# page1.net
KiCad netlist of a schematic drawn in EAGLE
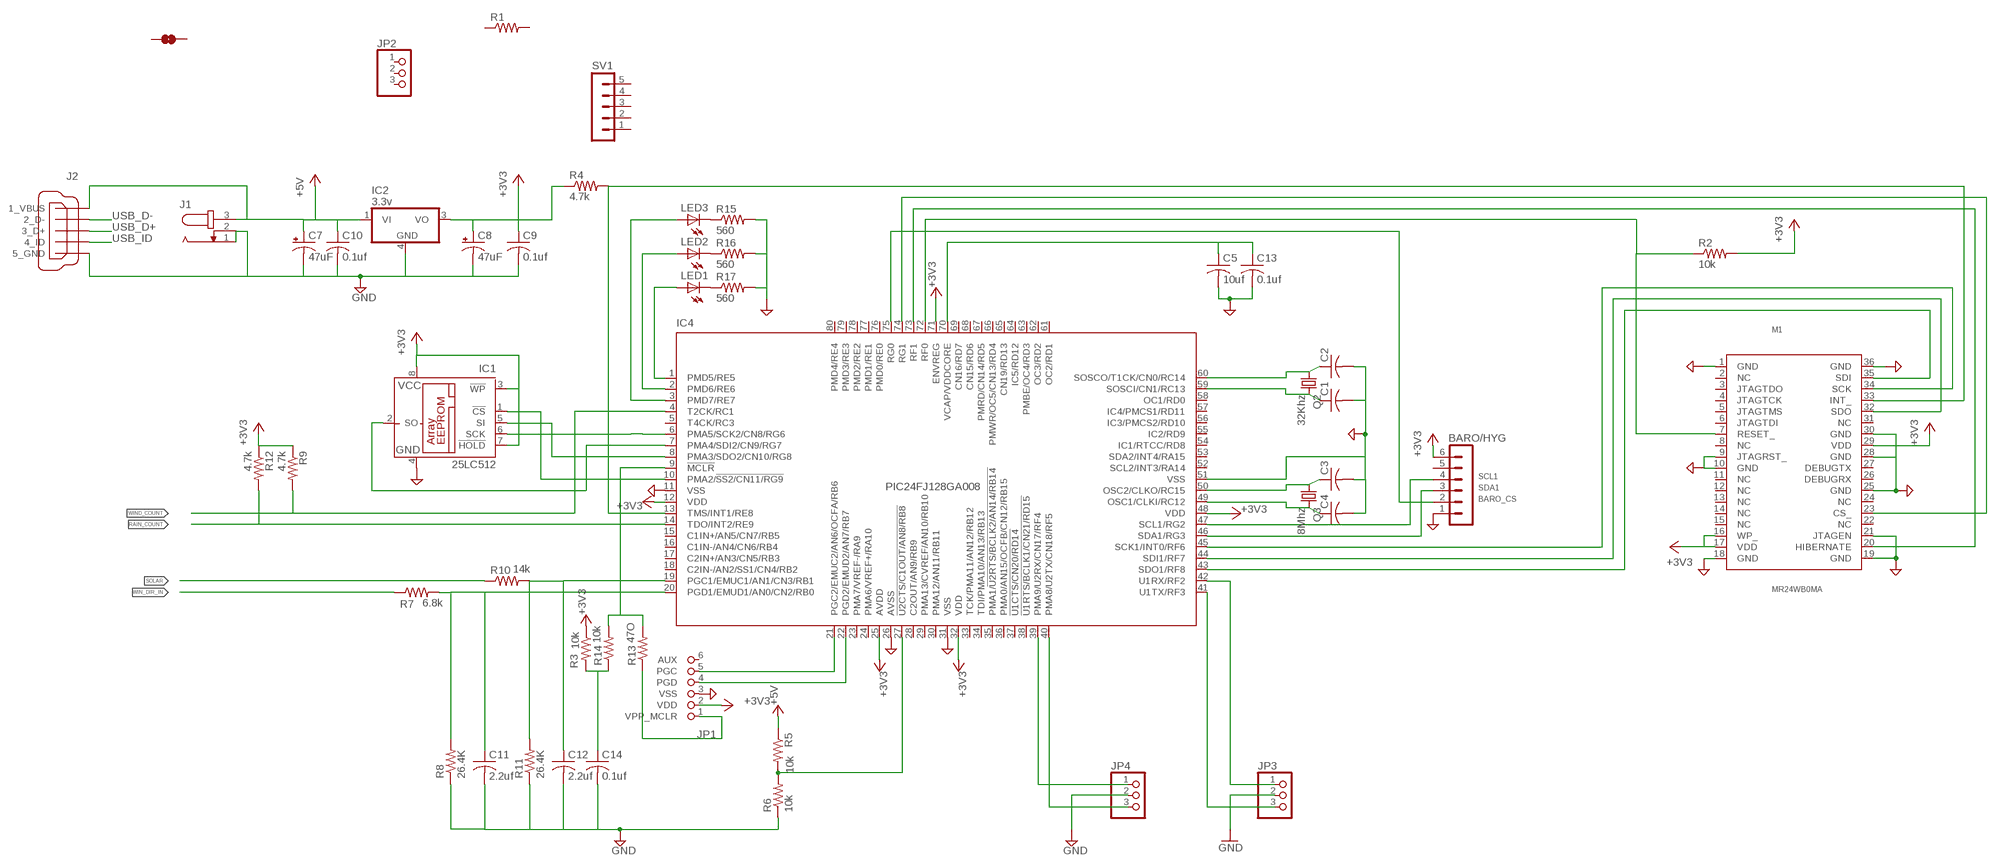
[diagram p0: schematic, sheet 1]

(export (version "E")
  (design (tool "Eeschema 10.0.6"))
  (components
    (comp (ref "BARO/HYG")
      (value "MA06-1")
      (footprint "eagle-import:MA06-1")
      (libsource (lib "eagle-import") (part "MA06-1"))
    )
    (comp (ref "C1")
      (value "C-USC0603")
      (footprint "eagle-import:C0603")
      (libsource (lib "eagle-import") (part "C-USC0603"))
    )
    (comp (ref "C2")
      (value "C-USC0603")
      (footprint "eagle-import:C0603")
      (libsource (lib "eagle-import") (part "C-USC0603"))
    )
    (comp (ref "C3")
      (value "C-USC0603")
      (footprint "eagle-import:C0603")
      (libsource (lib "eagle-import") (part "C-USC0603"))
    )
    (comp (ref "C4")
      (value "C-USC0603")
      (footprint "eagle-import:C0603")
      (libsource (lib "eagle-import") (part "C-USC0603"))
    )
    (comp (ref "C5")
      (value "10uf")
      (footprint "eagle-import:C0805")
      (libsource (lib "eagle-import") (part "C-USC0805"))
    )
    (comp (ref "C7")
      (value "47uF")
      (footprint "eagle-import:140CLH-0810")
      (libsource (lib "eagle-import") (part "CPOL-US140CLH-0810"))
    )
    (comp (ref "C8")
      (value "47uF")
      (footprint "eagle-import:140CLH-0810")
      (libsource (lib "eagle-import") (part "CPOL-US140CLH-0810"))
    )
    (comp (ref "C9")
      (value "0.1uf")
      (footprint "eagle-import:C0805")
      (libsource (lib "eagle-import") (part "C-USC0805"))
    )
    (comp (ref "C10")
      (value "0.1uf")
      (footprint "eagle-import:C0805")
      (libsource (lib "eagle-import") (part "C-USC0805"))
    )
    (comp (ref "C11")
      (value "2.2uf")
      (footprint "eagle-import:C1206")
      (libsource (lib "eagle-import") (part "C-USC1206"))
    )
    (comp (ref "C12")
      (value "2.2uf")
      (footprint "eagle-import:C1206")
      (libsource (lib "eagle-import") (part "C-USC1206"))
    )
    (comp (ref "C13")
      (value "0.1uf")
      (footprint "eagle-import:C0805")
      (libsource (lib "eagle-import") (part "C-USC0805"))
    )
    (comp (ref "C14")
      (value "0.1uf")
      (footprint "eagle-import:C0805")
      (libsource (lib "eagle-import") (part "C-USC0805"))
    )
    (comp (ref "IC1")
      (value "25LC512")
      (footprint "eagle-import:SO-08")
      (fields (field (name "MF") "MICROCHIP") (field (name "MPN") "25LC080/SN"))
      (libsource (lib "eagle-import") (part "25SNLC080"))
    )
    (comp (ref "IC2")
      (value "3.3v")
      (footprint "eagle-import:DPACK")
      (libsource (lib "eagle-import") (part "78MXXL"))
    )
    (comp (ref "IC4")
      (value "PIC24FJ128GA008")
      (footprint "eagle-import:TQFP80-12X12")
      (fields (field (name "MF") "MICROCHIP") (field (name "MPN") "PIC24FJ128GA008-I/PT"))
      (libsource (lib "eagle-import") (part "PIC24FJGA008128"))
    )
    (comp (ref "J1")
      (value "JACK-PLUG0")
      (footprint "eagle-import:SPC4077")
      (libsource (lib "eagle-import") (part "JACK-PLUG0"))
    )
    (comp (ref "J2")
      (value "MINI-USB-32005-201")
      (footprint "eagle-import:32005-201")
      (libsource (lib "eagle-import") (part "MINI-USB-32005-201"))
    )
    (comp (ref "JP1")
      (value "PIKIT2_PRG")
      (footprint "eagle-import:1X06")
      (libsource (lib "eagle-import") (part "PIKIT2_PRG"))
    )
    (comp (ref "JP2")
      (value "PINHD-1X3")
      (footprint "eagle-import:1X03")
      (libsource (lib "eagle-import") (part "PINHD-1X3"))
    )
    (comp (ref "JP3")
      (value "PINHD-1X3")
      (footprint "eagle-import:1X03")
      (libsource (lib "eagle-import") (part "PINHD-1X3"))
    )
    (comp (ref "JP4")
      (value "PINHD-1X3")
      (footprint "eagle-import:1X03")
      (libsource (lib "eagle-import") (part "PINHD-1X3"))
    )
    (comp (ref "LED1")
      (value "LEDCHIP-LED0603")
      (footprint "eagle-import:CHIP-LED0603")
      (libsource (lib "eagle-import") (part "LEDCHIP-LED0603"))
    )
    (comp (ref "LED2")
      (value "LEDCHIP-LED0603")
      (footprint "eagle-import:CHIP-LED0603")
      (libsource (lib "eagle-import") (part "LEDCHIP-LED0603"))
    )
    (comp (ref "LED3")
      (value "LEDCHIP-LED0603")
      (footprint "eagle-import:CHIP-LED0603")
      (libsource (lib "eagle-import") (part "LEDCHIP-LED0603"))
    )
    (comp (ref "M1")
      (value "MR24WB0MA")
      (footprint "eagle-import:MRF24W")
      (libsource (lib "eagle-import") (part "MR24WB0MA"))
    )
    (comp (ref "Q2")
      (value "32Khz")
      (footprint "eagle-import:TC26H")
      (libsource (lib "eagle-import") (part "CRYSTALTC26H"))
    )
    (comp (ref "Q3")
      (value "8Mhz")
      (footprint "eagle-import:HC49_S")
      (libsource (lib "eagle-import") (part "CRYSTALHC49S"))
    )
    (comp (ref "R1")
      (value "R-US_R0603")
      (footprint "eagle-import:R0603")
      (libsource (lib "eagle-import") (part "R-US_R0603"))
    )
    (comp (ref "R2")
      (value "10k")
      (footprint "eagle-import:R0603")
      (libsource (lib "eagle-import") (part "R-US_R0603"))
    )
    (comp (ref "R3")
      (value "10k")
      (footprint "eagle-import:R0603")
      (libsource (lib "eagle-import") (part "R-US_R0603"))
    )
    (comp (ref "R4")
      (value "4.7k")
      (footprint "eagle-import:R0603")
      (libsource (lib "eagle-import") (part "R-US_R0603"))
    )
    (comp (ref "R5")
      (value "10k")
      (footprint "eagle-import:R0603")
      (libsource (lib "eagle-import") (part "R-US_R0603"))
    )
    (comp (ref "R6")
      (value "10k")
      (footprint "eagle-import:R0603")
      (libsource (lib "eagle-import") (part "R-US_R0603"))
    )
    (comp (ref "R7")
      (value "6.8k")
      (footprint "eagle-import:R0603")
      (libsource (lib "eagle-import") (part "R-US_R0603"))
    )
    (comp (ref "R8")
      (value "26.4K")
      (footprint "eagle-import:R0603")
      (libsource (lib "eagle-import") (part "R-US_R0603"))
    )
    (comp (ref "R9")
      (value "4.7k")
      (footprint "eagle-import:R0603")
      (libsource (lib "eagle-import") (part "R-US_R0603"))
    )
    (comp (ref "R10")
      (value "14k")
      (footprint "eagle-import:R0603")
      (libsource (lib "eagle-import") (part "R-US_R0603"))
    )
    (comp (ref "R11")
      (value "26.4K")
      (footprint "eagle-import:R0603")
      (libsource (lib "eagle-import") (part "R-US_R0603"))
    )
    (comp (ref "R12")
      (value "4.7k")
      (footprint "eagle-import:R0603")
      (libsource (lib "eagle-import") (part "R-US_R0603"))
    )
    (comp (ref "R13")
      (value "47O")
      (footprint "eagle-import:R0603")
      (libsource (lib "eagle-import") (part "R-US_R0603"))
    )
    (comp (ref "R14")
      (value "10k")
      (footprint "eagle-import:R0603")
      (libsource (lib "eagle-import") (part "R-US_R0603"))
    )
    (comp (ref "R15")
      (value "560")
      (footprint "eagle-import:R0603")
      (libsource (lib "eagle-import") (part "R-US_R0603"))
    )
    (comp (ref "R16")
      (value "560")
      (footprint "eagle-import:R0603")
      (libsource (lib "eagle-import") (part "R-US_R0603"))
    )
    (comp (ref "R17")
      (value "560")
      (footprint "eagle-import:R0603")
      (libsource (lib "eagle-import") (part "R-US_R0603"))
    )
    (comp (ref "SV1")
      (value "MA05-1")
      (footprint "eagle-import:MA05-1")
      (libsource (lib "eagle-import") (part "MA05-1"))
    )
    (comp (ref "U$2")
      (value "SOLDERBRIDGE")
      (footprint "eagle-import:SOLDER_BRIDGE")
      (libsource (lib "eagle-import") (part "SOLDERBRIDGE"))
    )
  )
  (nets
    (net (code "1") (name "+3V3") (class "Default")
      (node (ref "BARO/HYG") (pin "6") (pinfunction "6_6") (pintype "passive"))
      (node (ref "C8") (pin "+") (pinfunction "+_+") (pintype "passive"))
      (node (ref "C9") (pin "1") (pinfunction "1_1") (pintype "passive"))
      (node (ref "IC1") (pin "3") (pinfunction "~{WP}_3") (pintype "input"))
      (node (ref "IC1") (pin "7") (pinfunction "~{HOLD}_7") (pintype "input"))
      (node (ref "IC1") (pin "8") (pinfunction "VCC_8") (pintype "power_in"))
      (node (ref "IC2") (pin "3") (pinfunction "VO_3") (pintype "passive"))
      (node (ref "IC4") (pin "12") (pinfunction "VDD_12") (pintype "power_in"))
      (node (ref "IC4") (pin "25") (pinfunction "AVDD_25") (pintype "power_in"))
      (node (ref "IC4") (pin "32") (pinfunction "VDD_32") (pintype "power_in"))
      (node (ref "IC4") (pin "48") (pinfunction "VDD_48") (pintype "power_in"))
      (node (ref "IC4") (pin "71") (pinfunction "ENVREG_71") (pintype "bidirectional"))
      (node (ref "JP1") (pin "2") (pinfunction "VDD_2") (pintype "passive"))
      (node (ref "M1") (pin "16") (pinfunction "WP__16") (pintype "bidirectional"))
      (node (ref "M1") (pin "17") (pinfunction "VDD_17") (pintype "bidirectional"))
      (node (ref "M1") (pin "29") (pinfunction "VDD_29") (pintype "bidirectional"))
      (node (ref "R12") (pin "1") (pinfunction "1_1") (pintype "passive"))
      (node (ref "R2") (pin "2") (pinfunction "2_2") (pintype "passive"))
      (node (ref "R3") (pin "1") (pinfunction "1_1") (pintype "passive"))
      (node (ref "R4") (pin "1") (pinfunction "1_1") (pintype "passive"))
      (node (ref "R9") (pin "1") (pinfunction "1_1") (pintype "passive"))
    )
    (net (code "2") (name "+5V") (class "Default")
      (node (ref "C10") (pin "1") (pinfunction "1_1") (pintype "passive"))
      (node (ref "C7") (pin "+") (pinfunction "+_+") (pintype "passive"))
      (node (ref "IC2") (pin "1") (pinfunction "VI_1") (pintype "input"))
      (node (ref "J1") (pin "3") (pinfunction "3_3") (pintype "passive"))
      (node (ref "J2") (pin "1_VBUS") (pinfunction "1_VBUS_1_VBUS") (pintype "passive"))
      (node (ref "R5") (pin "1") (pinfunction "1_1") (pintype "passive"))
    )
    (net (code "3") (name "/BARO_CS") (class "Default")
      (node (ref "BARO/HYG") (pin "2") (pinfunction "2_2") (pintype "passive"))
      (node (ref "IC4") (pin "75") (pinfunction "RG0_75") (pintype "bidirectional"))
    )
    (net (code "4") (name "/SCL1") (class "Default")
      (node (ref "BARO/HYG") (pin "4") (pinfunction "4_4") (pintype "passive"))
      (node (ref "IC4") (pin "47") (pinfunction "SCL1/RG2_47") (pintype "bidirectional"))
    )
    (net (code "5") (name "/SDA1") (class "Default")
      (node (ref "BARO/HYG") (pin "3") (pinfunction "3_3") (pintype "passive"))
      (node (ref "IC4") (pin "46") (pinfunction "SDA1/RG3_46") (pintype "bidirectional"))
    )
    (net (code "6") (name "/USB_D+") (class "Default")
      (node (ref "J2") (pin "3_D+") (pinfunction "3_D+_3_D+") (pintype "passive"))
    )
    (net (code "7") (name "/USB_D-") (class "Default")
      (node (ref "J2") (pin "2_D-") (pinfunction "2_D-_2_D-") (pintype "passive"))
    )
    (net (code "8") (name "/USB_ID") (class "Default")
      (node (ref "J2") (pin "4_ID") (pinfunction "4_ID_4_ID") (pintype "passive"))
    )
    (net (code "9") (name "GND") (class "Default")
      (node (ref "BARO/HYG") (pin "1") (pinfunction "1_1") (pintype "passive"))
      (node (ref "C1") (pin "2") (pinfunction "2_2") (pintype "passive"))
      (node (ref "C10") (pin "2") (pinfunction "2_2") (pintype "passive"))
      (node (ref "C11") (pin "2") (pinfunction "2_2") (pintype "passive"))
      (node (ref "C12") (pin "2") (pinfunction "2_2") (pintype "passive"))
      (node (ref "C13") (pin "2") (pinfunction "2_2") (pintype "passive"))
      (node (ref "C14") (pin "2") (pinfunction "2_2") (pintype "passive"))
      (node (ref "C2") (pin "2") (pinfunction "2_2") (pintype "passive"))
      (node (ref "C3") (pin "2") (pinfunction "2_2") (pintype "passive"))
      (node (ref "C4") (pin "2") (pinfunction "2_2") (pintype "passive"))
      (node (ref "C5") (pin "2") (pinfunction "2_2") (pintype "passive"))
      (node (ref "C7") (pin "-") (pinfunction "-_-") (pintype "passive"))
      (node (ref "C8") (pin "-") (pinfunction "-_-") (pintype "passive"))
      (node (ref "C9") (pin "2") (pinfunction "2_2") (pintype "passive"))
      (node (ref "IC1") (pin "4") (pinfunction "GND_4") (pintype "power_in"))
      (node (ref "IC2") (pin "4") (pinfunction "GND_4") (pintype "passive"))
      (node (ref "IC4") (pin "11") (pinfunction "VSS_11") (pintype "power_in"))
      (node (ref "IC4") (pin "26") (pinfunction "AVSS_26") (pintype "power_in"))
      (node (ref "IC4") (pin "31") (pinfunction "VSS_31") (pintype "power_in"))
      (node (ref "IC4") (pin "51") (pinfunction "VSS_51") (pintype "power_in"))
      (node (ref "J1") (pin "1") (pinfunction "1_1") (pintype "passive"))
      (node (ref "J1") (pin "2") (pinfunction "2_2") (pintype "passive"))
      (node (ref "J2") (pin "5_USB_GND") (pinfunction "5_GND_5_USB_GND") (pintype "passive"))
      (node (ref "JP1") (pin "3") (pinfunction "VSS_3") (pintype "passive"))
      (node (ref "JP3") (pin "2") (pinfunction "2_2") (pintype "passive"))
      (node (ref "JP4") (pin "2") (pinfunction "2_2") (pintype "passive"))
      (node (ref "M1") (pin "1") (pinfunction "GND_1") (pintype "bidirectional"))
      (node (ref "M1") (pin "10") (pinfunction "GND_10") (pintype "bidirectional"))
      (node (ref "M1") (pin "18") (pinfunction "GND_18") (pintype "bidirectional"))
      (node (ref "M1") (pin "19") (pinfunction "GND_19") (pintype "bidirectional"))
      (node (ref "M1") (pin "21") (pinfunction "JTAGEN_21") (pintype "bidirectional"))
      (node (ref "M1") (pin "25") (pinfunction "GND_25") (pintype "bidirectional"))
      (node (ref "M1") (pin "28") (pinfunction "GND_28") (pintype "bidirectional"))
      (node (ref "M1") (pin "30") (pinfunction "GND_30") (pintype "bidirectional"))
      (node (ref "M1") (pin "36") (pinfunction "GND_36") (pintype "bidirectional"))
      (node (ref "M1") (pin "9") (pinfunction "JTAGRST__9") (pintype "bidirectional"))
      (node (ref "R11") (pin "1") (pinfunction "1_1") (pintype "passive"))
      (node (ref "R15") (pin "2") (pinfunction "2_2") (pintype "passive"))
      (node (ref "R16") (pin "2") (pinfunction "2_2") (pintype "passive"))
      (node (ref "R17") (pin "2") (pinfunction "2_2") (pintype "passive"))
      (node (ref "R6") (pin "1") (pinfunction "1_1") (pintype "passive"))
      (node (ref "R8") (pin "1") (pinfunction "1_1") (pintype "passive"))
    )
    (net (code "10") (name "Net-(C14-Pad1)") (class "Default")
      (node (ref "C14") (pin "1") (pinfunction "1_1") (pintype "passive"))
      (node (ref "R14") (pin "1") (pinfunction "1_1") (pintype "passive"))
      (node (ref "R3") (pin "2") (pinfunction "2_2") (pintype "passive"))
    )
    (net (code "11") (name "Net-(IC1-SCK)") (class "Default")
      (node (ref "IC1") (pin "6") (pinfunction "SCK_6") (pintype "input"))
      (node (ref "IC4") (pin "6") (pinfunction "PMA5/SCK2/CN8/RG6_6") (pintype "bidirectional"))
    )
    (net (code "12") (name "Net-(IC1-SI)") (class "Default")
      (node (ref "IC1") (pin "5") (pinfunction "SI_5") (pintype "input"))
      (node (ref "IC4") (pin "8") (pinfunction "PMA3/SDO2/CN10/RG8_8") (pintype "bidirectional"))
    )
    (net (code "13") (name "Net-(IC1-SO)") (class "Default")
      (node (ref "IC1") (pin "2") (pinfunction "SO_2") (pintype "bidirectional"))
      (node (ref "IC4") (pin "7") (pinfunction "PMA4/SDI2/CN9/RG7_7") (pintype "bidirectional"))
    )
    (net (code "14") (name "Net-(IC1-~{CS})") (class "Default")
      (node (ref "IC1") (pin "1") (pinfunction "~{CS}_1") (pintype "input"))
      (node (ref "IC4") (pin "10") (pinfunction "PMA2/~{SS2/CN11/RG9}_10") (pintype "bidirectional"))
    )
    (net (code "15") (name "Net-(IC4-OSC1{slash}CLKI{slash}RC12)") (class "Default")
      (node (ref "C4") (pin "1") (pinfunction "1_1") (pintype "passive"))
      (node (ref "IC4") (pin "49") (pinfunction "OSC1/CLKI/RC12_49") (pintype "bidirectional"))
      (node (ref "Q3") (pin "2") (pinfunction "2_2") (pintype "passive"))
    )
    (net (code "16") (name "Net-(IC4-OSC2{slash}CLKO{slash}RC15)") (class "Default")
      (node (ref "C3") (pin "1") (pinfunction "1_1") (pintype "passive"))
      (node (ref "IC4") (pin "50") (pinfunction "OSC2/CLKO/RC15_50") (pintype "bidirectional"))
      (node (ref "Q3") (pin "1") (pinfunction "1_1") (pintype "passive"))
    )
    (net (code "17") (name "Net-(IC4-PGC1{slash}EMUC1{slash}AN1{slash}CN3{slash}RB1)") (class "Default")
      (node (ref "C12") (pin "1") (pinfunction "1_1") (pintype "passive"))
      (node (ref "IC4") (pin "19") (pinfunction "PGC1/EMUC1/AN1/CN3/RB1_19") (pintype "bidirectional"))
      (node (ref "R10") (pin "2") (pinfunction "2_2") (pintype "passive"))
      (node (ref "R11") (pin "2") (pinfunction "2_2") (pintype "passive"))
    )
    (net (code "18") (name "Net-(IC4-PGC2{slash}EMUC2{slash}AN6{slash}OCFA{slash}RB6)") (class "Default")
      (node (ref "IC4") (pin "21") (pinfunction "PGC2/EMUC2/AN6/OCFA/RB6_21") (pintype "bidirectional"))
      (node (ref "JP1") (pin "5") (pinfunction "PGC_5") (pintype "passive"))
    )
    (net (code "19") (name "Net-(IC4-PGD1{slash}EMUD1{slash}AN0{slash}CN2{slash}RB0)") (class "Default")
      (node (ref "C11") (pin "1") (pinfunction "1_1") (pintype "passive"))
      (node (ref "IC4") (pin "20") (pinfunction "PGD1/EMUD1/AN0/CN2/RB0_20") (pintype "bidirectional"))
      (node (ref "R7") (pin "2") (pinfunction "2_2") (pintype "passive"))
      (node (ref "R8") (pin "2") (pinfunction "2_2") (pintype "passive"))
    )
    (net (code "20") (name "Net-(IC4-PGD2{slash}EMUD2{slash}AN7{slash}RB7)") (class "Default")
      (node (ref "IC4") (pin "22") (pinfunction "PGD2/EMUD2/AN7/RB7_22") (pintype "bidirectional"))
      (node (ref "JP1") (pin "4") (pinfunction "PGD_4") (pintype "passive"))
    )
    (net (code "21") (name "Net-(IC4-PMA8{slash}U2TX{slash}CN18{slash}RF5)") (class "Default")
      (node (ref "IC4") (pin "40") (pinfunction "PMA8/U2TX/CN18/RF5_40") (pintype "bidirectional"))
      (node (ref "JP4") (pin "3") (pinfunction "3_3") (pintype "passive"))
    )
    (net (code "22") (name "Net-(IC4-PMA9{slash}U2RX{slash}CN17{slash}RF4)") (class "Default")
      (node (ref "IC4") (pin "39") (pinfunction "PMA9/U2RX/CN17/RF4_39") (pintype "bidirectional"))
      (node (ref "JP4") (pin "1") (pinfunction "1_1") (pintype "passive"))
    )
    (net (code "23") (name "Net-(IC4-PMD5{slash}RE5)") (class "Default")
      (node (ref "IC4") (pin "1") (pinfunction "PMD5/RE5_1") (pintype "bidirectional"))
      (node (ref "LED1") (pin "A") (pinfunction "A_A") (pintype "passive"))
    )
    (net (code "24") (name "Net-(IC4-PMD6{slash}RE6)") (class "Default")
      (node (ref "IC4") (pin "2") (pinfunction "PMD6/RE6_2") (pintype "bidirectional"))
      (node (ref "LED2") (pin "A") (pinfunction "A_A") (pintype "passive"))
    )
    (net (code "25") (name "Net-(IC4-PMD7{slash}RE7)") (class "Default")
      (node (ref "IC4") (pin "3") (pinfunction "PMD7/RE7_3") (pintype "bidirectional"))
      (node (ref "LED3") (pin "A") (pinfunction "A_A") (pintype "passive"))
    )
    (net (code "26") (name "Net-(IC4-RF0)") (class "Default")
      (node (ref "IC4") (pin "72") (pinfunction "RF0_72") (pintype "bidirectional"))
      (node (ref "M1") (pin "7") (pinfunction "RESET__7") (pintype "bidirectional"))
      (node (ref "R2") (pin "1") (pinfunction "1_1") (pintype "passive"))
    )
    (net (code "27") (name "Net-(IC4-RF1)") (class "Default")
      (node (ref "IC4") (pin "73") (pinfunction "RF1_73") (pintype "bidirectional"))
      (node (ref "M1") (pin "20") (pinfunction "HIBERNATE_20") (pintype "bidirectional"))
    )
    (net (code "28") (name "Net-(IC4-RG1)") (class "Default")
      (node (ref "IC4") (pin "74") (pinfunction "RG1_74") (pintype "bidirectional"))
      (node (ref "M1") (pin "23") (pinfunction "CS__23") (pintype "bidirectional"))
    )
    (net (code "29") (name "Net-(IC4-SCK1{slash}INT0{slash}RF6)") (class "Default")
      (node (ref "IC4") (pin "45") (pinfunction "SCK1/INT0/RF6_45") (pintype "bidirectional"))
      (node (ref "M1") (pin "34") (pinfunction "SCK_34") (pintype "bidirectional"))
    )
    (net (code "30") (name "Net-(IC4-SDI1{slash}RF7)") (class "Default")
      (node (ref "IC4") (pin "44") (pinfunction "SDI1/RF7_44") (pintype "bidirectional"))
      (node (ref "M1") (pin "32") (pinfunction "SDO_32") (pintype "bidirectional"))
    )
    (net (code "31") (name "Net-(IC4-SDO1{slash}RF8)") (class "Default")
      (node (ref "IC4") (pin "43") (pinfunction "SDO1/RF8_43") (pintype "bidirectional"))
      (node (ref "M1") (pin "35") (pinfunction "SDI_35") (pintype "bidirectional"))
    )
    (net (code "32") (name "Net-(IC4-SOSCI{slash}CN1{slash}RC13)") (class "Default")
      (node (ref "C1") (pin "1") (pinfunction "1_1") (pintype "passive"))
      (node (ref "IC4") (pin "59") (pinfunction "SOSCI/CN1/RC13_59") (pintype "bidirectional"))
      (node (ref "Q2") (pin "2") (pinfunction "2_2") (pintype "passive"))
    )
    (net (code "33") (name "Net-(IC4-SOSCO{slash}T1CK{slash}CN0{slash}RC14)") (class "Default")
      (node (ref "C2") (pin "1") (pinfunction "1_1") (pintype "passive"))
      (node (ref "IC4") (pin "60") (pinfunction "SOSCO/T1CK/CN0/RC14_60") (pintype "bidirectional"))
      (node (ref "Q2") (pin "1") (pinfunction "1_1") (pintype "passive"))
    )
    (net (code "34") (name "Net-(IC4-TMS{slash}INT1{slash}RE8)") (class "Default")
      (node (ref "IC4") (pin "13") (pinfunction "TMS/INT1/RE8_13") (pintype "bidirectional"))
      (node (ref "M1") (pin "33") (pinfunction "INT__33") (pintype "bidirectional"))
      (node (ref "R4") (pin "2") (pinfunction "2_2") (pintype "passive"))
    )
    (net (code "35") (name "Net-(IC4-U1RX{slash}RF2)") (class "Default")
      (node (ref "IC4") (pin "42") (pinfunction "U1RX/RF2_42") (pintype "bidirectional"))
      (node (ref "JP3") (pin "1") (pinfunction "1_1") (pintype "passive"))
    )
    (net (code "36") (name "Net-(IC4-U1TX{slash}RF3)") (class "Default")
      (node (ref "IC4") (pin "41") (pinfunction "U1TX/RF3_41") (pintype "bidirectional"))
      (node (ref "JP3") (pin "3") (pinfunction "3_3") (pintype "passive"))
    )
    (net (code "37") (name "Net-(IC4-VCAP{slash}VDDCORE)") (class "Default")
      (node (ref "C13") (pin "1") (pinfunction "1_1") (pintype "passive"))
      (node (ref "C5") (pin "1") (pinfunction "1_1") (pintype "passive"))
      (node (ref "IC4") (pin "70") (pinfunction "VCAP/VDDCORE_70") (pintype "bidirectional"))
    )
    (net (code "38") (name "Net-(IC4-~{MCLR})") (class "Default")
      (node (ref "IC4") (pin "9") (pinfunction "~{MCLR}_9") (pintype "bidirectional"))
      (node (ref "R13") (pin "2") (pinfunction "2_2") (pintype "passive"))
      (node (ref "R14") (pin "2") (pinfunction "2_2") (pintype "passive"))
    )
    (net (code "39") (name "Net-(IC4-~{U2CTS{slash}C1OUT{slash}AN8{slash}RB8})") (class "Default")
      (node (ref "IC4") (pin "27") (pinfunction "~{U2CTS/C1OUT/AN8/RB8}_27") (pintype "bidirectional"))
      (node (ref "R5") (pin "2") (pinfunction "2_2") (pintype "passive"))
      (node (ref "R6") (pin "2") (pinfunction "2_2") (pintype "passive"))
    )
    (net (code "40") (name "Net-(JP1-VPP_MCLR)") (class "Default")
      (node (ref "JP1") (pin "1") (pinfunction "VPP_MCLR_1") (pintype "passive"))
      (node (ref "R13") (pin "1") (pinfunction "1_1") (pintype "passive"))
    )
    (net (code "41") (name "Net-(LED1-PadC)") (class "Default")
      (node (ref "LED1") (pin "C") (pinfunction "C_C") (pintype "passive"))
      (node (ref "R17") (pin "1") (pinfunction "1_1") (pintype "passive"))
    )
    (net (code "42") (name "Net-(LED2-PadC)") (class "Default")
      (node (ref "LED2") (pin "C") (pinfunction "C_C") (pintype "passive"))
      (node (ref "R16") (pin "1") (pinfunction "1_1") (pintype "passive"))
    )
    (net (code "43") (name "Net-(LED3-PadC)") (class "Default")
      (node (ref "LED3") (pin "C") (pinfunction "C_C") (pintype "passive"))
      (node (ref "R15") (pin "1") (pinfunction "1_1") (pintype "passive"))
    )
    (net (code "44") (name "RAIN_COUNT") (class "Default")
      (node (ref "IC4") (pin "14") (pinfunction "TDO/INT2/RE9_14") (pintype "bidirectional"))
      (node (ref "R12") (pin "2") (pinfunction "2_2") (pintype "passive"))
    )
    (net (code "45") (name "SOLAR") (class "Default")
      (node (ref "R10") (pin "1") (pinfunction "1_1") (pintype "passive"))
    )
    (net (code "46") (name "WIND_COUNT") (class "Default")
      (node (ref "IC4") (pin "4") (pinfunction "T2CK/RC1_4") (pintype "bidirectional"))
      (node (ref "R9") (pin "2") (pinfunction "2_2") (pintype "passive"))
    )
    (net (code "47") (name "WIN_DIR_IN") (class "Default")
      (node (ref "R7") (pin "1") (pinfunction "1_1") (pintype "passive"))
    )
    (net (code "48") (name "unconnected-(BARO/HYG-Pad5)") (class "Default")
      (node (ref "BARO/HYG") (pin "5") (pinfunction "5_5") (pintype "passive"))
    )
    (net (code "49") (name "unconnected-(IC4-C1IN+{slash}AN5{slash}CN7{slash}RB5-Pad15)") (class "Default")
      (node (ref "IC4") (pin "15") (pinfunction "C1IN+/AN5/CN7/RB5_15") (pintype "bidirectional"))
    )
    (net (code "50") (name "unconnected-(IC4-C1IN-{slash}AN4{slash}CN6{slash}RB4-Pad16)") (class "Default")
      (node (ref "IC4") (pin "16") (pinfunction "C1IN-/AN4/CN6/RB4_16") (pintype "bidirectional"))
    )
    (net (code "51") (name "unconnected-(IC4-C2IN+{slash}AN3{slash}CN5{slash}RB3-Pad17)") (class "Default")
      (node (ref "IC4") (pin "17") (pinfunction "C2IN+/AN3/CN5/RB3_17") (pintype "bidirectional"))
    )
    (net (code "52") (name "unconnected-(IC4-C2IN-{slash}AN2{slash}SS1{slash}CN4{slash}RB2-Pad18)") (class "Default")
      (node (ref "IC4") (pin "18") (pinfunction "C2IN-/AN2/SS1/CN4/RB2_18") (pintype "bidirectional"))
    )
    (net (code "53") (name "unconnected-(IC4-C2OUT{slash}AN9{slash}RB9-Pad28)") (class "Default")
      (node (ref "IC4") (pin "28") (pinfunction "C2OUT/AN9/RB9_28") (pintype "bidirectional"))
    )
    (net (code "54") (name "unconnected-(IC4-CN15{slash}RD6-Pad68)") (class "Default")
      (node (ref "IC4") (pin "68") (pinfunction "CN15/RD6_68") (pintype "bidirectional"))
    )
    (net (code "55") (name "unconnected-(IC4-CN16{slash}RD7-Pad69)") (class "Default")
      (node (ref "IC4") (pin "69") (pinfunction "CN16/RD7_69") (pintype "bidirectional"))
    )
    (net (code "56") (name "unconnected-(IC4-CN19{slash}RD13-Pad65)") (class "Default")
      (node (ref "IC4") (pin "65") (pinfunction "CN19/RD13_65") (pintype "bidirectional"))
    )
    (net (code "57") (name "unconnected-(IC4-IC1{slash}RTCC{slash}RD8-Pad54)") (class "Default")
      (node (ref "IC4") (pin "54") (pinfunction "IC1/RTCC/RD8_54") (pintype "bidirectional"))
    )
    (net (code "58") (name "unconnected-(IC4-IC2{slash}RD9-Pad55)") (class "Default")
      (node (ref "IC4") (pin "55") (pinfunction "IC2/RD9_55") (pintype "bidirectional"))
    )
    (net (code "59") (name "unconnected-(IC4-IC3{slash}PMCS2{slash}RD10-Pad56)") (class "Default")
      (node (ref "IC4") (pin "56") (pinfunction "IC3/PMCS2/RD10_56") (pintype "bidirectional"))
    )
    (net (code "60") (name "unconnected-(IC4-IC4{slash}PMCS1{slash}RD11-Pad57)") (class "Default")
      (node (ref "IC4") (pin "57") (pinfunction "IC4/PMCS1/RD11_57") (pintype "bidirectional"))
    )
    (net (code "61") (name "unconnected-(IC4-IC5{slash}RD12-Pad64)") (class "Default")
      (node (ref "IC4") (pin "64") (pinfunction "IC5/RD12_64") (pintype "bidirectional"))
    )
    (net (code "62") (name "unconnected-(IC4-OC1{slash}RD0-Pad58)") (class "Default")
      (node (ref "IC4") (pin "58") (pinfunction "OC1/RD0_58") (pintype "bidirectional"))
    )
    (net (code "63") (name "unconnected-(IC4-OC2{slash}RD1-Pad61)") (class "Default")
      (node (ref "IC4") (pin "61") (pinfunction "OC2/RD1_61") (pintype "bidirectional"))
    )
    (net (code "64") (name "unconnected-(IC4-OC3{slash}RD2-Pad62)") (class "Default")
      (node (ref "IC4") (pin "62") (pinfunction "OC3/RD2_62") (pintype "bidirectional"))
    )
    (net (code "65") (name "unconnected-(IC4-PMA0{slash}AN15{slash}OCFB{slash}CN12{slash}RB15-Pad36)") (class "Default")
      (node (ref "IC4") (pin "36") (pinfunction "PMA0/AN15/OCFB/CN12/RB15_36") (pintype "bidirectional"))
    )
    (net (code "66") (name "unconnected-(IC4-PMA1{slash}~{U2RTS{slash}BCLK2{slash}AN14{slash}RB14}-Pad35)") (class "Default")
      (node (ref "IC4") (pin "35") (pinfunction "PMA1/~{U2RTS/BCLK2/AN14/RB14}_35") (pintype "bidirectional"))
    )
    (net (code "67") (name "unconnected-(IC4-PMA6{slash}VREF+{slash}RA10-Pad24)") (class "Default")
      (node (ref "IC4") (pin "24") (pinfunction "PMA6/VREF+/RA10_24") (pintype "bidirectional"))
    )
    (net (code "68") (name "unconnected-(IC4-PMA7{slash}VREF-{slash}RA9-Pad23)") (class "Default")
      (node (ref "IC4") (pin "23") (pinfunction "PMA7/VREF-/RA9_23") (pintype "bidirectional"))
    )
    (net (code "69") (name "unconnected-(IC4-PMA12{slash}AN11{slash}RB11-Pad30)") (class "Default")
      (node (ref "IC4") (pin "30") (pinfunction "PMA12/AN11/RB11_30") (pintype "bidirectional"))
    )
    (net (code "70") (name "unconnected-(IC4-PMA13{slash}CVREF{slash}AN10{slash}RB10-Pad29)") (class "Default")
      (node (ref "IC4") (pin "29") (pinfunction "PMA13/CVREF/AN10/RB10_29") (pintype "bidirectional"))
    )
    (net (code "71") (name "unconnected-(IC4-PMBE{slash}OC4{slash}RD3-Pad63)") (class "Default")
      (node (ref "IC4") (pin "63") (pinfunction "PMBE/OC4/RD3_63") (pintype "bidirectional"))
    )
    (net (code "72") (name "unconnected-(IC4-PMD0{slash}RE0-Pad76)") (class "Default")
      (node (ref "IC4") (pin "76") (pinfunction "PMD0/RE0_76") (pintype "bidirectional"))
    )
    (net (code "73") (name "unconnected-(IC4-PMD1{slash}RE1-Pad77)") (class "Default")
      (node (ref "IC4") (pin "77") (pinfunction "PMD1/RE1_77") (pintype "bidirectional"))
    )
    (net (code "74") (name "unconnected-(IC4-PMD2{slash}RE2-Pad78)") (class "Default")
      (node (ref "IC4") (pin "78") (pinfunction "PMD2/RE2_78") (pintype "bidirectional"))
    )
    (net (code "75") (name "unconnected-(IC4-PMD3{slash}RE3-Pad79)") (class "Default")
      (node (ref "IC4") (pin "79") (pinfunction "PMD3/RE3_79") (pintype "bidirectional"))
    )
    (net (code "76") (name "unconnected-(IC4-PMD4{slash}RE4-Pad80)") (class "Default")
      (node (ref "IC4") (pin "80") (pinfunction "PMD4/RE4_80") (pintype "bidirectional"))
    )
    (net (code "77") (name "unconnected-(IC4-PMRD{slash}CN14{slash}RD5-Pad67)") (class "Default")
      (node (ref "IC4") (pin "67") (pinfunction "PMRD/CN14/RD5_67") (pintype "bidirectional"))
    )
    (net (code "78") (name "unconnected-(IC4-PMWR{slash}OC5{slash}CN13{slash}RD4-Pad66)") (class "Default")
      (node (ref "IC4") (pin "66") (pinfunction "PMWR/OC5/CN13/RD4_66") (pintype "bidirectional"))
    )
    (net (code "79") (name "unconnected-(IC4-SCL2{slash}INT3{slash}RA14-Pad52)") (class "Default")
      (node (ref "IC4") (pin "52") (pinfunction "SCL2/INT3/RA14_52") (pintype "bidirectional"))
    )
    (net (code "80") (name "unconnected-(IC4-SDA2{slash}INT4{slash}RA15-Pad53)") (class "Default")
      (node (ref "IC4") (pin "53") (pinfunction "SDA2/INT4/RA15_53") (pintype "bidirectional"))
    )
    (net (code "81") (name "unconnected-(IC4-T4CK{slash}RC3-Pad5)") (class "Default")
      (node (ref "IC4") (pin "5") (pinfunction "T4CK/RC3_5") (pintype "bidirectional"))
    )
    (net (code "82") (name "unconnected-(IC4-TCK{slash}PMA11{slash}AN12{slash}RB12-Pad33)") (class "Default")
      (node (ref "IC4") (pin "33") (pinfunction "TCK/PMA11/AN12/RB12_33") (pintype "bidirectional"))
    )
    (net (code "83") (name "unconnected-(IC4-TDI{slash}PMA10{slash}AN13{slash}RB13-Pad34)") (class "Default")
      (node (ref "IC4") (pin "34") (pinfunction "TDI/PMA10/AN13/RB13_34") (pintype "bidirectional"))
    )
    (net (code "84") (name "unconnected-(IC4-~{U1CTS{slash}CN20{slash}RD14}-Pad37)") (class "Default")
      (node (ref "IC4") (pin "37") (pinfunction "~{U1CTS/CN20/RD14}_37") (pintype "bidirectional"))
    )
    (net (code "85") (name "unconnected-(IC4-~{U1RTS{slash}BCLK1{slash}CN21{slash}RD15}-Pad38)") (class "Default")
      (node (ref "IC4") (pin "38") (pinfunction "~{U1RTS/BCLK1/CN21/RD15}_38") (pintype "bidirectional"))
    )
    (net (code "86") (name "unconnected-(JP1-AUX-Pad6)") (class "Default")
      (node (ref "JP1") (pin "6") (pinfunction "AUX_6") (pintype "passive"))
    )
    (net (code "87") (name "unconnected-(JP2-Pad1)") (class "Default")
      (node (ref "JP2") (pin "1") (pinfunction "1_1") (pintype "passive"))
    )
    (net (code "88") (name "unconnected-(JP2-Pad2)") (class "Default")
      (node (ref "JP2") (pin "2") (pinfunction "2_2") (pintype "passive"))
    )
    (net (code "89") (name "unconnected-(JP2-Pad3)") (class "Default")
      (node (ref "JP2") (pin "3") (pinfunction "3_3") (pintype "passive"))
    )
    (net (code "90") (name "unconnected-(M1-DEBUGRX-Pad26)") (class "Default")
      (node (ref "M1") (pin "26") (pinfunction "DEBUGRX_26") (pintype "bidirectional"))
    )
    (net (code "91") (name "unconnected-(M1-DEBUGTX-Pad27)") (class "Default")
      (node (ref "M1") (pin "27") (pinfunction "DEBUGTX_27") (pintype "bidirectional"))
    )
    (net (code "92") (name "unconnected-(M1-JTAGTCK-Pad4)") (class "Default")
      (node (ref "M1") (pin "4") (pinfunction "JTAGTCK_4") (pintype "bidirectional"))
    )
    (net (code "93") (name "unconnected-(M1-JTAGTDI-Pad6)") (class "Default")
      (node (ref "M1") (pin "6") (pinfunction "JTAGTDI_6") (pintype "bidirectional"))
    )
    (net (code "94") (name "unconnected-(M1-JTAGTDO-Pad3)") (class "Default")
      (node (ref "M1") (pin "3") (pinfunction "JTAGTDO_3") (pintype "bidirectional"))
    )
    (net (code "95") (name "unconnected-(M1-JTAGTMS-Pad5)") (class "Default")
      (node (ref "M1") (pin "5") (pinfunction "JTAGTMS_5") (pintype "bidirectional"))
    )
    (net (code "96") (name "unconnected-(M1-NC-Pad2)") (class "Default")
      (node (ref "M1") (pin "2") (pinfunction "NC_2") (pintype "bidirectional"))
    )
    (net (code "97") (name "unconnected-(M1-NC-Pad8)") (class "Default")
      (node (ref "M1") (pin "8") (pinfunction "NC_8") (pintype "bidirectional"))
    )
    (net (code "98") (name "unconnected-(M1-NC-Pad11)") (class "Default")
      (node (ref "M1") (pin "11") (pinfunction "NC_11") (pintype "bidirectional"))
    )
    (net (code "99") (name "unconnected-(M1-NC-Pad12)") (class "Default")
      (node (ref "M1") (pin "12") (pinfunction "NC_12") (pintype "bidirectional"))
    )
    (net (code "100") (name "unconnected-(M1-NC-Pad13)") (class "Default")
      (node (ref "M1") (pin "13") (pinfunction "NC_13") (pintype "bidirectional"))
    )
    (net (code "101") (name "unconnected-(M1-NC-Pad14)") (class "Default")
      (node (ref "M1") (pin "14") (pinfunction "NC_14") (pintype "bidirectional"))
    )
    (net (code "102") (name "unconnected-(M1-NC-Pad15)") (class "Default")
      (node (ref "M1") (pin "15") (pinfunction "NC_15") (pintype "bidirectional"))
    )
    (net (code "103") (name "unconnected-(M1-NC-Pad22)") (class "Default")
      (node (ref "M1") (pin "22") (pinfunction "NC_22") (pintype "bidirectional"))
    )
    (net (code "104") (name "unconnected-(M1-NC-Pad24)") (class "Default")
      (node (ref "M1") (pin "24") (pinfunction "NC_24") (pintype "bidirectional"))
    )
    (net (code "105") (name "unconnected-(M1-NC-Pad31)") (class "Default")
      (node (ref "M1") (pin "31") (pinfunction "NC_31") (pintype "bidirectional"))
    )
    (net (code "106") (name "unconnected-(R1-Pad1)") (class "Default")
      (node (ref "R1") (pin "1") (pinfunction "1_1") (pintype "passive"))
    )
    (net (code "107") (name "unconnected-(R1-Pad2)") (class "Default")
      (node (ref "R1") (pin "2") (pinfunction "2_2") (pintype "passive"))
    )
    (net (code "108") (name "unconnected-(SV1-Pad1)") (class "Default")
      (node (ref "SV1") (pin "1") (pinfunction "1_1") (pintype "passive"))
    )
    (net (code "109") (name "unconnected-(SV1-Pad2)") (class "Default")
      (node (ref "SV1") (pin "2") (pinfunction "2_2") (pintype "passive"))
    )
    (net (code "110") (name "unconnected-(SV1-Pad3)") (class "Default")
      (node (ref "SV1") (pin "3") (pinfunction "3_3") (pintype "passive"))
    )
    (net (code "111") (name "unconnected-(SV1-Pad4)") (class "Default")
      (node (ref "SV1") (pin "4") (pinfunction "4_4") (pintype "passive"))
    )
    (net (code "112") (name "unconnected-(SV1-Pad5)") (class "Default")
      (node (ref "SV1") (pin "5") (pinfunction "5_5") (pintype "passive"))
    )
    (net (code "113") (name "unconnected-(U$2-PadP$1)") (class "Default")
      (node (ref "U$2") (pin "P$1") (pinfunction "P$1_P$1") (pintype "bidirectional"))
    )
    (net (code "114") (name "unconnected-(U$2-PadP$2)") (class "Default")
      (node (ref "U$2") (pin "P$2") (pinfunction "P$2_P$2") (pintype "bidirectional"))
    )
  )
)
